# ZYNQ-DDR3L.net
KiCad netlist of a schematic drawn in Altium Designer
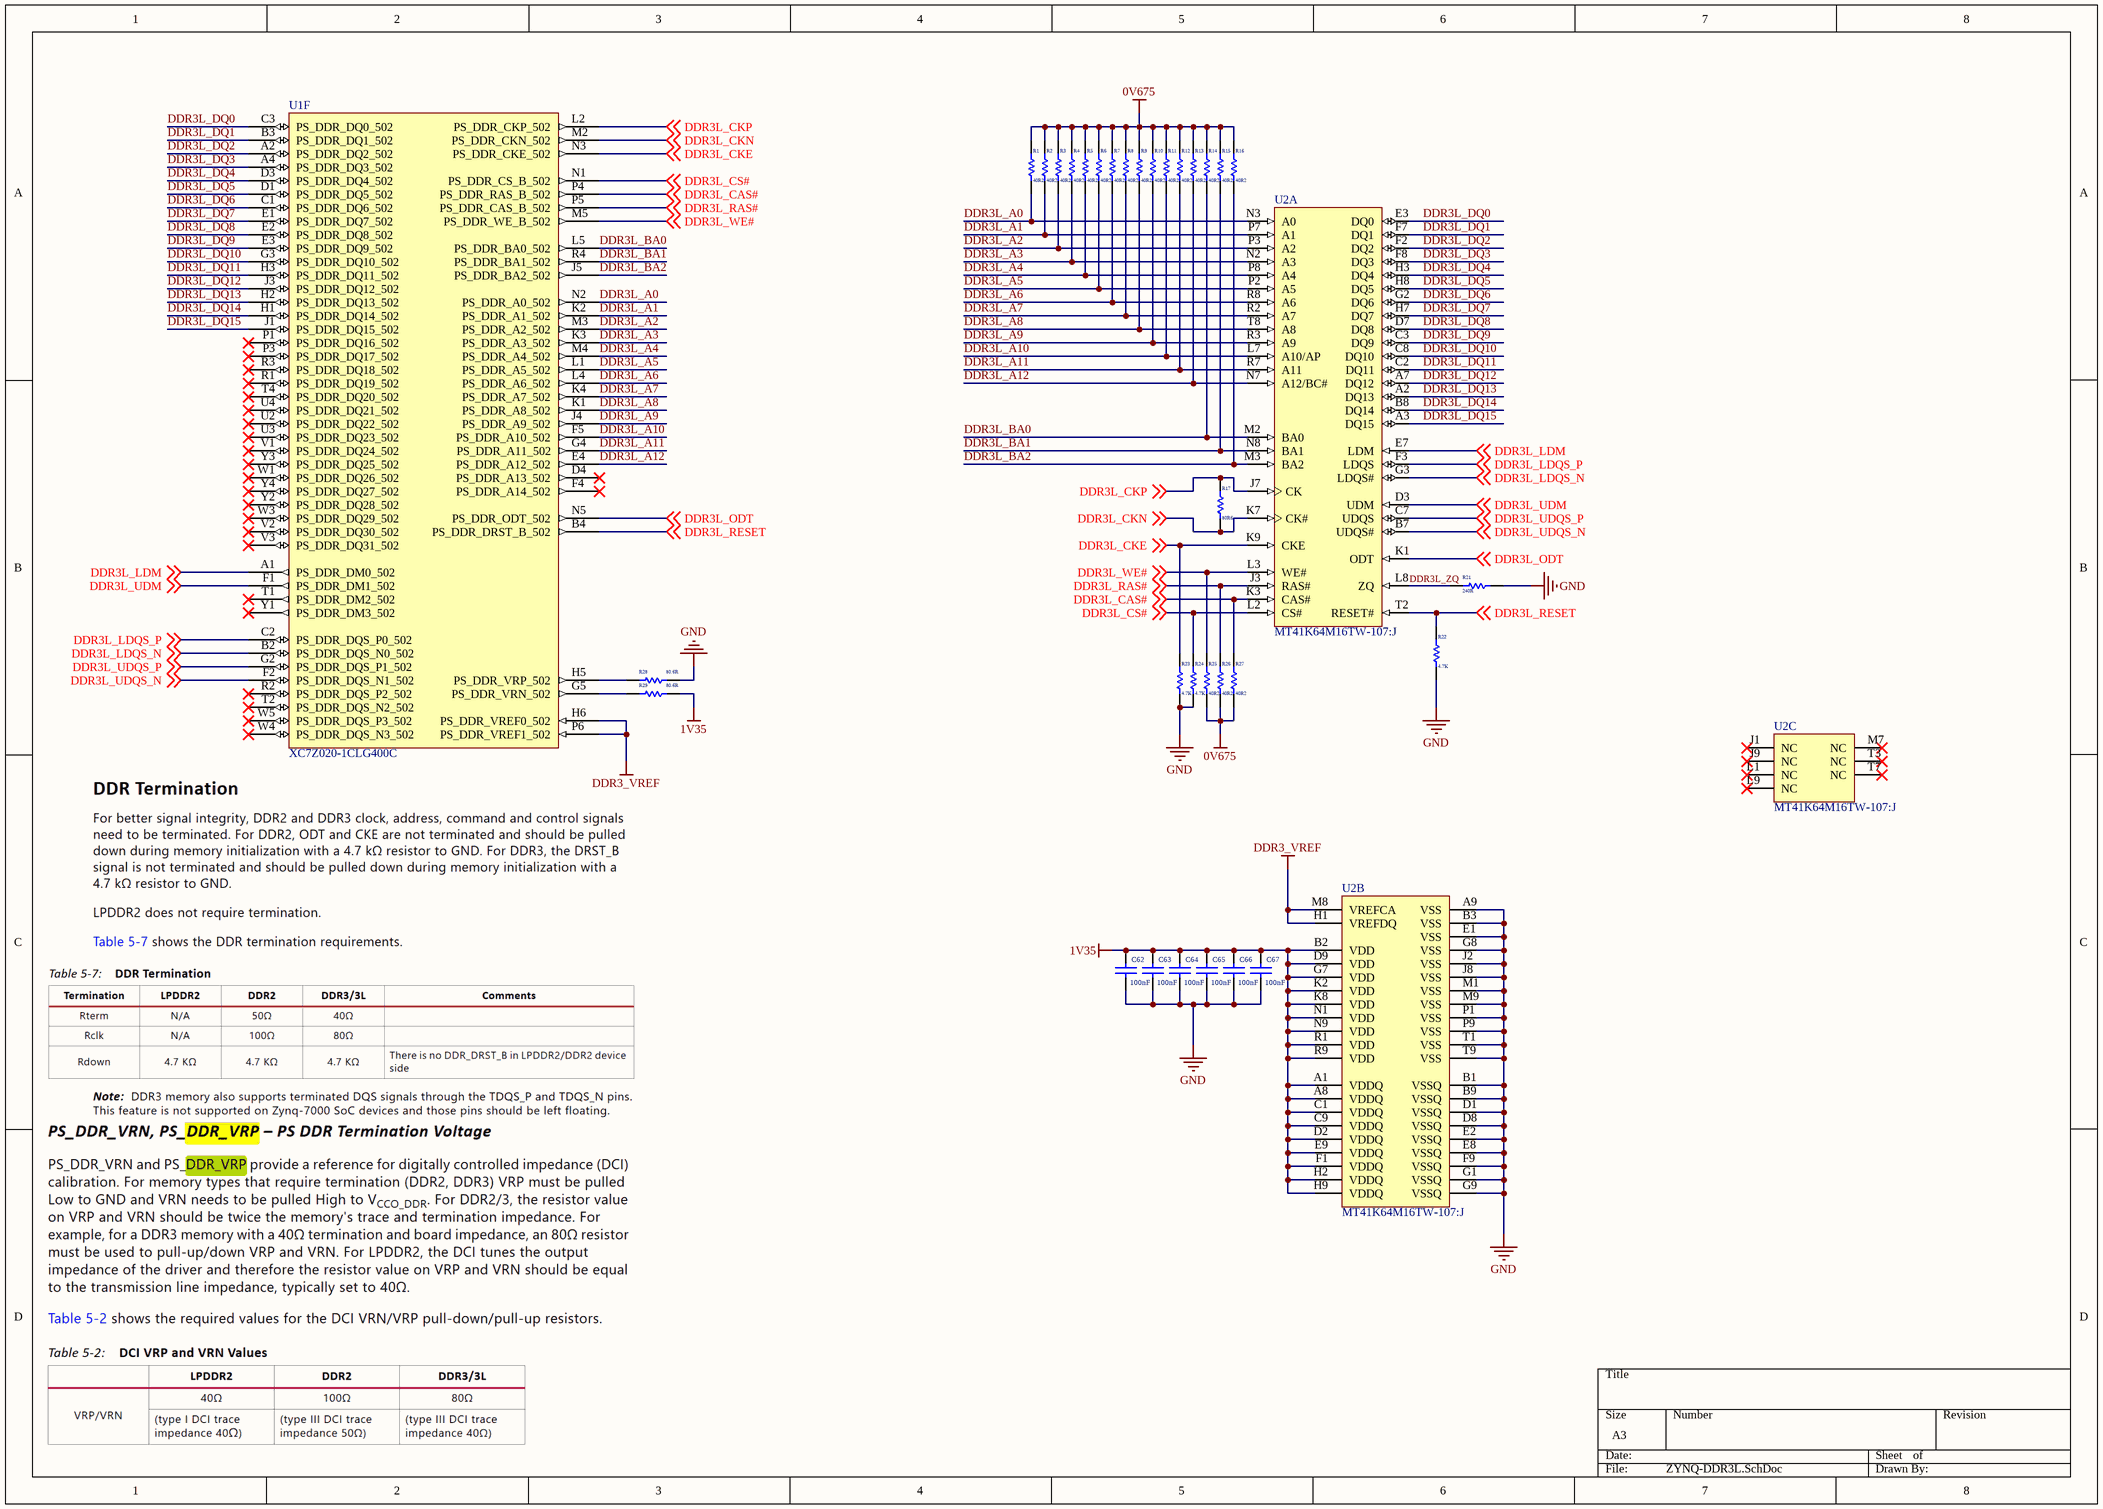
[diagram p0: ZYNQ-DDR3L.SchDoc]

(export (version "E")
  (design (tool "Eeschema 10.0.6"))
  (components
    (comp (ref "C62")
      (value "100nF")
      (footprint "CAPC1005X55X25LL05T10")
      (fields (field (name "PART NUMBER") "GRM155R71H104KE14D") (field (name "MANUFACTURER") "Murata"))
      (libsource (lib "Altium Content Vault") (part "CAP"))
    )
    (comp (ref "C63")
      (value "100nF")
      (footprint "CAPC1005X55X25LL05T10")
      (fields (field (name "PART NUMBER") "GRM155R71H104KE14D") (field (name "MANUFACTURER") "Murata"))
      (libsource (lib "Altium Content Vault") (part "CAP"))
    )
    (comp (ref "C64")
      (value "100nF")
      (footprint "CAPC1005X55X25LL05T10")
      (fields (field (name "PART NUMBER") "GRM155R71H104KE14D") (field (name "MANUFACTURER") "Murata"))
      (libsource (lib "Altium Content Vault") (part "CAP"))
    )
    (comp (ref "C65")
      (value "100nF")
      (footprint "CAPC1005X55X25LL05T10")
      (fields (field (name "PART NUMBER") "GRM155R71H104KE14D") (field (name "MANUFACTURER") "Murata"))
      (libsource (lib "Altium Content Vault") (part "CAP"))
    )
    (comp (ref "C66")
      (value "100nF")
      (footprint "CAPC1005X55X25LL05T10")
      (fields (field (name "PART NUMBER") "GRM155R71H104KE14D") (field (name "MANUFACTURER") "Murata"))
      (libsource (lib "Altium Content Vault") (part "CAP"))
    )
    (comp (ref "C67")
      (value "100nF")
      (footprint "CAPC1005X55X25LL05T10")
      (fields (field (name "PART NUMBER") "GRM155R71H104KE14D") (field (name "MANUFACTURER") "Murata"))
      (libsource (lib "Altium Content Vault") (part "CAP"))
    )
    (comp (ref "R1")
      (value "40R2")
      (footprint "RESC1005X40X25LL05T05")
      (fields (field (name "MANUFACTURER") "Panasonic") (field (name "PART NUMBER") "ERJ-2RKF40R2X"))
      (libsource (lib "Altium Content Vault") (part "RES"))
    )
    (comp (ref "R2")
      (value "40R2")
      (footprint "RESC1005X40X25LL05T05")
      (fields (field (name "MANUFACTURER") "Panasonic") (field (name "PART NUMBER") "ERJ-2RKF40R2X"))
      (libsource (lib "Altium Content Vault") (part "RES"))
    )
    (comp (ref "R3")
      (value "40R2")
      (footprint "RESC1005X40X25LL05T05")
      (fields (field (name "MANUFACTURER") "Panasonic") (field (name "PART NUMBER") "ERJ-2RKF40R2X"))
      (libsource (lib "Altium Content Vault") (part "RES"))
    )
    (comp (ref "R4")
      (value "40R2")
      (footprint "RESC1005X40X25LL05T05")
      (fields (field (name "MANUFACTURER") "Panasonic") (field (name "PART NUMBER") "ERJ-2RKF40R2X"))
      (libsource (lib "Altium Content Vault") (part "RES"))
    )
    (comp (ref "R5")
      (value "40R2")
      (footprint "RESC1005X40X25LL05T05")
      (fields (field (name "MANUFACTURER") "Panasonic") (field (name "PART NUMBER") "ERJ-2RKF40R2X"))
      (libsource (lib "Altium Content Vault") (part "RES"))
    )
    (comp (ref "R6")
      (value "40R2")
      (footprint "RESC1005X40X25LL05T05")
      (fields (field (name "MANUFACTURER") "Panasonic") (field (name "PART NUMBER") "ERJ-2RKF40R2X"))
      (libsource (lib "Altium Content Vault") (part "RES"))
    )
    (comp (ref "R7")
      (value "40R2")
      (footprint "RESC1005X40X25LL05T05")
      (fields (field (name "MANUFACTURER") "Panasonic") (field (name "PART NUMBER") "ERJ-2RKF40R2X"))
      (libsource (lib "Altium Content Vault") (part "RES"))
    )
    (comp (ref "R8")
      (value "40R2")
      (footprint "RESC1005X40X25LL05T05")
      (fields (field (name "MANUFACTURER") "Panasonic") (field (name "PART NUMBER") "ERJ-2RKF40R2X"))
      (libsource (lib "Altium Content Vault") (part "RES"))
    )
    (comp (ref "R9")
      (value "40R2")
      (footprint "RESC1005X40X25LL05T05")
      (fields (field (name "MANUFACTURER") "Panasonic") (field (name "PART NUMBER") "ERJ-2RKF40R2X"))
      (libsource (lib "Altium Content Vault") (part "RES"))
    )
    (comp (ref "R10")
      (value "40R2")
      (footprint "RESC1005X40X25LL05T05")
      (fields (field (name "MANUFACTURER") "Panasonic") (field (name "PART NUMBER") "ERJ-2RKF40R2X"))
      (libsource (lib "Altium Content Vault") (part "RES"))
    )
    (comp (ref "R11")
      (value "40R2")
      (footprint "RESC1005X40X25LL05T05")
      (fields (field (name "MANUFACTURER") "Panasonic") (field (name "PART NUMBER") "ERJ-2RKF40R2X"))
      (libsource (lib "Altium Content Vault") (part "RES"))
    )
    (comp (ref "R12")
      (value "40R2")
      (footprint "RESC1005X40X25LL05T05")
      (fields (field (name "MANUFACTURER") "Panasonic") (field (name "PART NUMBER") "ERJ-2RKF40R2X"))
      (libsource (lib "Altium Content Vault") (part "RES"))
    )
    (comp (ref "R13")
      (value "40R2")
      (footprint "RESC1005X40X25LL05T05")
      (fields (field (name "MANUFACTURER") "Panasonic") (field (name "PART NUMBER") "ERJ-2RKF40R2X"))
      (libsource (lib "Altium Content Vault") (part "RES"))
    )
    (comp (ref "R14")
      (value "40R2")
      (footprint "RESC1005X40X25LL05T05")
      (fields (field (name "MANUFACTURER") "Panasonic") (field (name "PART NUMBER") "ERJ-2RKF40R2X"))
      (libsource (lib "Altium Content Vault") (part "RES"))
    )
    (comp (ref "R15")
      (value "40R2")
      (footprint "RESC1005X40X25LL05T05")
      (fields (field (name "MANUFACTURER") "Panasonic") (field (name "PART NUMBER") "ERJ-2RKF40R2X"))
      (libsource (lib "Altium Content Vault") (part "RES"))
    )
    (comp (ref "R16")
      (value "40R2")
      (footprint "RESC1005X40X25LL05T05")
      (fields (field (name "MANUFACTURER") "Panasonic") (field (name "PART NUMBER") "ERJ-2RKF40R2X"))
      (libsource (lib "Altium Content Vault") (part "RES"))
    )
    (comp (ref "R17")
      (value "80R6")
      (footprint "RESC1005X40X25LL05T05")
      (fields (field (name "MANUFACTURER") "Panasonic") (field (name "PART NUMBER") "ERJ-2RKF40R2X"))
      (libsource (lib "Altium Content Vault") (part "RES"))
    )
    (comp (ref "R21")
      (value "240R")
      (footprint "RESC1005X40X25LL05T05")
      (fields (field (name "MANUFACTURER") "Panasonic") (field (name "PART NUMBER") "ERJ-2RKF40R2X"))
      (libsource (lib "Altium Content Vault") (part "RES"))
    )
    (comp (ref "R22")
      (value "4.7K")
      (footprint "RESC1005X40X25LL05T05")
      (fields (field (name "MANUFACTURER") "Panasonic") (field (name "PART NUMBER") "ERJ-2RKF40R2X"))
      (libsource (lib "Altium Content Vault") (part "RES"))
    )
    (comp (ref "R23")
      (value "4.7K")
      (footprint "RESC1005X40X25LL05T05")
      (fields (field (name "MANUFACTURER") "Panasonic") (field (name "PART NUMBER") "ERJ-2RKF40R2X"))
      (libsource (lib "Altium Content Vault") (part "RES"))
    )
    (comp (ref "R24")
      (value "4.7K")
      (footprint "RESC1005X40X25LL05T05")
      (fields (field (name "MANUFACTURER") "Panasonic") (field (name "PART NUMBER") "ERJ-2RKF40R2X"))
      (libsource (lib "Altium Content Vault") (part "RES"))
    )
    (comp (ref "R25")
      (value "40R2")
      (footprint "RESC1005X40X25LL05T05")
      (fields (field (name "MANUFACTURER") "Panasonic") (field (name "PART NUMBER") "ERJ-2RKF40R2X"))
      (libsource (lib "Altium Content Vault") (part "RES"))
    )
    (comp (ref "R26")
      (value "40R2")
      (footprint "RESC1005X40X25LL05T05")
      (fields (field (name "MANUFACTURER") "Panasonic") (field (name "PART NUMBER") "ERJ-2RKF40R2X"))
      (libsource (lib "Altium Content Vault") (part "RES"))
    )
    (comp (ref "R27")
      (value "40R2")
      (footprint "RESC1005X40X25LL05T05")
      (fields (field (name "MANUFACTURER") "Panasonic") (field (name "PART NUMBER") "ERJ-2RKF40R2X"))
      (libsource (lib "Altium Content Vault") (part "RES"))
    )
    (comp (ref "R28")
      (value "80.6R")
      (footprint "RESC1005X40X25LL05T05")
      (fields (field (name "MANUFACTURER") "Panasonic") (field (name "PART NUMBER") "ERJ-2RKF40R2X"))
      (libsource (lib "Altium Content Vault") (part "RES"))
    )
    (comp (ref "R29")
      (value "80.6R")
      (footprint "RESC1005X40X25LL05T05")
      (fields (field (name "MANUFACTURER") "Panasonic") (field (name "PART NUMBER") "ERJ-2RKF40R2X"))
      (libsource (lib "Altium Content Vault") (part "RES"))
    )
    (comp (ref "U1")
      (value "XC7Z020-1CLG400C")
      (footprint "CLG400")
      (fields (field (name "GENERIC PART NUMBER") "XC7Z020"))
      (libsource (lib "Altium Content Vault") (part "XNLX-XC7Z020-CLG400"))
    )
    (comp (ref "U2")
      (value "MT41K64M16TW-107:J")
      (footprint "MICT-TW-96")
      (description "DDR3L SDRAM, 8 Meg x 16 x 8 Bank, 1.07 ns, 0 to 95 degC, 96-Ball FBGA (TW), Pb-Free")
      (fields (field (name "MANUFACTURER") "Micron"))
      (libsource (lib "Altium Content Vault") (part "MICT-MT41K_1G-FBGA96"))
    )
  )
  (nets
    (net (code "1") (name "/DDR3L_A0") (class "Default")
      (node (ref "R1") (pin "1") (pinfunction "1_1") (pintype "passive"))
      (node (ref "U1") (pin "N2") (pinfunction "PS_DDR_A0_502_N2") (pintype "output"))
      (node (ref "U2") (pin "N3") (pinfunction "A0_N3") (pintype "input"))
    )
    (net (code "2") (name "/DDR3L_A1") (class "Default")
      (node (ref "R2") (pin "1") (pinfunction "1_1") (pintype "passive"))
      (node (ref "U1") (pin "K2") (pinfunction "PS_DDR_A1_502_K2") (pintype "output"))
      (node (ref "U2") (pin "P7") (pinfunction "A1_P7") (pintype "input"))
    )
    (net (code "3") (name "/DDR3L_A2") (class "Default")
      (node (ref "R3") (pin "1") (pinfunction "1_1") (pintype "passive"))
      (node (ref "U1") (pin "M3") (pinfunction "PS_DDR_A2_502_M3") (pintype "output"))
      (node (ref "U2") (pin "P3") (pinfunction "A2_P3") (pintype "input"))
    )
    (net (code "4") (name "/DDR3L_A3") (class "Default")
      (node (ref "R4") (pin "1") (pinfunction "1_1") (pintype "passive"))
      (node (ref "U1") (pin "K3") (pinfunction "PS_DDR_A3_502_K3") (pintype "output"))
      (node (ref "U2") (pin "N2") (pinfunction "A3_N2") (pintype "input"))
    )
    (net (code "5") (name "/DDR3L_A4") (class "Default")
      (node (ref "R5") (pin "1") (pinfunction "1_1") (pintype "passive"))
      (node (ref "U1") (pin "M4") (pinfunction "PS_DDR_A4_502_M4") (pintype "output"))
      (node (ref "U2") (pin "P8") (pinfunction "A4_P8") (pintype "input"))
    )
    (net (code "6") (name "/DDR3L_A5") (class "Default")
      (node (ref "R6") (pin "1") (pinfunction "1_1") (pintype "passive"))
      (node (ref "U1") (pin "L1") (pinfunction "PS_DDR_A5_502_L1") (pintype "output"))
      (node (ref "U2") (pin "P2") (pinfunction "A5_P2") (pintype "input"))
    )
    (net (code "7") (name "/DDR3L_A6") (class "Default")
      (node (ref "R7") (pin "1") (pinfunction "1_1") (pintype "passive"))
      (node (ref "U1") (pin "L4") (pinfunction "PS_DDR_A6_502_L4") (pintype "output"))
      (node (ref "U2") (pin "R8") (pinfunction "A6_R8") (pintype "input"))
    )
    (net (code "8") (name "/DDR3L_A7") (class "Default")
      (node (ref "R8") (pin "1") (pinfunction "1_1") (pintype "passive"))
      (node (ref "U1") (pin "K4") (pinfunction "PS_DDR_A7_502_K4") (pintype "output"))
      (node (ref "U2") (pin "R2") (pinfunction "A7_R2") (pintype "input"))
    )
    (net (code "9") (name "/DDR3L_A8") (class "Default")
      (node (ref "R9") (pin "1") (pinfunction "1_1") (pintype "passive"))
      (node (ref "U1") (pin "K1") (pinfunction "PS_DDR_A8_502_K1") (pintype "output"))
      (node (ref "U2") (pin "T8") (pinfunction "A8_T8") (pintype "input"))
    )
    (net (code "10") (name "/DDR3L_A9") (class "Default")
      (node (ref "R10") (pin "1") (pinfunction "1_1") (pintype "passive"))
      (node (ref "U1") (pin "J4") (pinfunction "PS_DDR_A9_502_J4") (pintype "output"))
      (node (ref "U2") (pin "R3") (pinfunction "A9_R3") (pintype "input"))
    )
    (net (code "11") (name "/DDR3L_A10") (class "Default")
      (node (ref "R11") (pin "1") (pinfunction "1_1") (pintype "passive"))
      (node (ref "U1") (pin "F5") (pinfunction "PS_DDR_A10_502_F5") (pintype "output"))
      (node (ref "U2") (pin "L7") (pinfunction "A10/AP_L7") (pintype "input"))
    )
    (net (code "12") (name "/DDR3L_A11") (class "Default")
      (node (ref "R12") (pin "1") (pinfunction "1_1") (pintype "passive"))
      (node (ref "U1") (pin "G4") (pinfunction "PS_DDR_A11_502_G4") (pintype "output"))
      (node (ref "U2") (pin "R7") (pinfunction "A11_R7") (pintype "input"))
    )
    (net (code "13") (name "/DDR3L_A12") (class "Default")
      (node (ref "R13") (pin "1") (pinfunction "1_1") (pintype "passive"))
      (node (ref "U1") (pin "E4") (pinfunction "PS_DDR_A12_502_E4") (pintype "output"))
      (node (ref "U2") (pin "N7") (pinfunction "A12/BC#_N7") (pintype "input"))
    )
    (net (code "14") (name "/DDR3L_BA0") (class "Default")
      (node (ref "R14") (pin "1") (pinfunction "1_1") (pintype "passive"))
      (node (ref "U1") (pin "L5") (pinfunction "PS_DDR_BA0_502_L5") (pintype "output"))
      (node (ref "U2") (pin "M2") (pinfunction "BA0_M2") (pintype "input"))
    )
    (net (code "15") (name "/DDR3L_BA1") (class "Default")
      (node (ref "R15") (pin "1") (pinfunction "1_1") (pintype "passive"))
      (node (ref "U1") (pin "R4") (pinfunction "PS_DDR_BA1_502_R4") (pintype "output"))
      (node (ref "U2") (pin "N8") (pinfunction "BA1_N8") (pintype "input"))
    )
    (net (code "16") (name "/DDR3L_BA2") (class "Default")
      (node (ref "R16") (pin "1") (pinfunction "1_1") (pintype "passive"))
      (node (ref "U1") (pin "J5") (pinfunction "PS_DDR_BA2_502_J5") (pintype "output"))
      (node (ref "U2") (pin "M3") (pinfunction "BA2_M3") (pintype "input"))
    )
    (net (code "17") (name "/DDR3L_DQ0") (class "Default")
      (node (ref "U1") (pin "C3") (pinfunction "PS_DDR_DQ0_502_C3") (pintype "bidirectional"))
      (node (ref "U2") (pin "E3") (pinfunction "DQ0_E3") (pintype "bidirectional"))
    )
    (net (code "18") (name "/DDR3L_DQ1") (class "Default")
      (node (ref "U1") (pin "B3") (pinfunction "PS_DDR_DQ1_502_B3") (pintype "bidirectional"))
      (node (ref "U2") (pin "F7") (pinfunction "DQ1_F7") (pintype "bidirectional"))
    )
    (net (code "19") (name "/DDR3L_DQ2") (class "Default")
      (node (ref "U1") (pin "A2") (pinfunction "PS_DDR_DQ2_502_A2") (pintype "bidirectional"))
      (node (ref "U2") (pin "F2") (pinfunction "DQ2_F2") (pintype "bidirectional"))
    )
    (net (code "20") (name "/DDR3L_DQ3") (class "Default")
      (node (ref "U1") (pin "A4") (pinfunction "PS_DDR_DQ3_502_A4") (pintype "bidirectional"))
      (node (ref "U2") (pin "F8") (pinfunction "DQ3_F8") (pintype "bidirectional"))
    )
    (net (code "21") (name "/DDR3L_DQ4") (class "Default")
      (node (ref "U1") (pin "D3") (pinfunction "PS_DDR_DQ4_502_D3") (pintype "bidirectional"))
      (node (ref "U2") (pin "H3") (pinfunction "DQ4_H3") (pintype "bidirectional"))
    )
    (net (code "22") (name "/DDR3L_DQ5") (class "Default")
      (node (ref "U1") (pin "D1") (pinfunction "PS_DDR_DQ5_502_D1") (pintype "bidirectional"))
      (node (ref "U2") (pin "H8") (pinfunction "DQ5_H8") (pintype "bidirectional"))
    )
    (net (code "23") (name "/DDR3L_DQ6") (class "Default")
      (node (ref "U1") (pin "C1") (pinfunction "PS_DDR_DQ6_502_C1") (pintype "bidirectional"))
      (node (ref "U2") (pin "G2") (pinfunction "DQ6_G2") (pintype "bidirectional"))
    )
    (net (code "24") (name "/DDR3L_DQ7") (class "Default")
      (node (ref "U1") (pin "E1") (pinfunction "PS_DDR_DQ7_502_E1") (pintype "bidirectional"))
      (node (ref "U2") (pin "H7") (pinfunction "DQ7_H7") (pintype "bidirectional"))
    )
    (net (code "25") (name "/DDR3L_DQ8") (class "Default")
      (node (ref "U1") (pin "E2") (pinfunction "PS_DDR_DQ8_502_E2") (pintype "bidirectional"))
      (node (ref "U2") (pin "D7") (pinfunction "DQ8_D7") (pintype "bidirectional"))
    )
    (net (code "26") (name "/DDR3L_DQ9") (class "Default")
      (node (ref "U1") (pin "E3") (pinfunction "PS_DDR_DQ9_502_E3") (pintype "bidirectional"))
      (node (ref "U2") (pin "C3") (pinfunction "DQ9_C3") (pintype "bidirectional"))
    )
    (net (code "27") (name "/DDR3L_DQ10") (class "Default")
      (node (ref "U1") (pin "G3") (pinfunction "PS_DDR_DQ10_502_G3") (pintype "bidirectional"))
      (node (ref "U2") (pin "C8") (pinfunction "DQ10_C8") (pintype "bidirectional"))
    )
    (net (code "28") (name "/DDR3L_DQ11") (class "Default")
      (node (ref "U1") (pin "H3") (pinfunction "PS_DDR_DQ11_502_H3") (pintype "bidirectional"))
      (node (ref "U2") (pin "C2") (pinfunction "DQ11_C2") (pintype "bidirectional"))
    )
    (net (code "29") (name "/DDR3L_DQ12") (class "Default")
      (node (ref "U1") (pin "J3") (pinfunction "PS_DDR_DQ12_502_J3") (pintype "bidirectional"))
      (node (ref "U2") (pin "A7") (pinfunction "DQ12_A7") (pintype "bidirectional"))
    )
    (net (code "30") (name "/DDR3L_DQ13") (class "Default")
      (node (ref "U1") (pin "H2") (pinfunction "PS_DDR_DQ13_502_H2") (pintype "bidirectional"))
      (node (ref "U2") (pin "A2") (pinfunction "DQ13_A2") (pintype "bidirectional"))
    )
    (net (code "31") (name "/DDR3L_DQ14") (class "Default")
      (node (ref "U1") (pin "H1") (pinfunction "PS_DDR_DQ14_502_H1") (pintype "bidirectional"))
      (node (ref "U2") (pin "B8") (pinfunction "DQ14_B8") (pintype "bidirectional"))
    )
    (net (code "32") (name "/DDR3L_DQ15") (class "Default")
      (node (ref "U1") (pin "J1") (pinfunction "PS_DDR_DQ15_502_J1") (pintype "bidirectional"))
      (node (ref "U2") (pin "A3") (pinfunction "DQ15_A3") (pintype "bidirectional"))
    )
    (net (code "33") (name "/DDR3L_ZQ") (class "Default")
      (node (ref "R21") (pin "2") (pinfunction "2_2") (pintype "passive"))
      (node (ref "U2") (pin "L8") (pinfunction "ZQ_L8") (pintype "input"))
    )
    (net (code "34") (name "0V675") (class "Default")
      (node (ref "R1") (pin "2") (pinfunction "2_2") (pintype "passive"))
      (node (ref "R10") (pin "2") (pinfunction "2_2") (pintype "passive"))
      (node (ref "R11") (pin "2") (pinfunction "2_2") (pintype "passive"))
      (node (ref "R12") (pin "2") (pinfunction "2_2") (pintype "passive"))
      (node (ref "R13") (pin "2") (pinfunction "2_2") (pintype "passive"))
      (node (ref "R14") (pin "2") (pinfunction "2_2") (pintype "passive"))
      (node (ref "R15") (pin "2") (pinfunction "2_2") (pintype "passive"))
      (node (ref "R16") (pin "2") (pinfunction "2_2") (pintype "passive"))
      (node (ref "R2") (pin "2") (pinfunction "2_2") (pintype "passive"))
      (node (ref "R25") (pin "1") (pinfunction "1_1") (pintype "passive"))
      (node (ref "R26") (pin "1") (pinfunction "1_1") (pintype "passive"))
      (node (ref "R27") (pin "1") (pinfunction "1_1") (pintype "passive"))
      (node (ref "R3") (pin "2") (pinfunction "2_2") (pintype "passive"))
      (node (ref "R4") (pin "2") (pinfunction "2_2") (pintype "passive"))
      (node (ref "R5") (pin "2") (pinfunction "2_2") (pintype "passive"))
      (node (ref "R6") (pin "2") (pinfunction "2_2") (pintype "passive"))
      (node (ref "R7") (pin "2") (pinfunction "2_2") (pintype "passive"))
      (node (ref "R8") (pin "2") (pinfunction "2_2") (pintype "passive"))
      (node (ref "R9") (pin "2") (pinfunction "2_2") (pintype "passive"))
    )
    (net (code "35") (name "1V35") (class "Default")
      (node (ref "C62") (pin "2") (pinfunction "2_2") (pintype "passive"))
      (node (ref "C63") (pin "2") (pinfunction "2_2") (pintype "passive"))
      (node (ref "C64") (pin "2") (pinfunction "2_2") (pintype "passive"))
      (node (ref "C65") (pin "2") (pinfunction "2_2") (pintype "passive"))
      (node (ref "C66") (pin "2") (pinfunction "2_2") (pintype "passive"))
      (node (ref "C67") (pin "2") (pinfunction "2_2") (pintype "passive"))
      (node (ref "R29") (pin "1") (pinfunction "1_1") (pintype "passive"))
      (node (ref "U2") (pin "A1") (pinfunction "VDDQ_A1") (pintype "power_in"))
      (node (ref "U2") (pin "A8") (pinfunction "VDDQ_A8") (pintype "power_in"))
      (node (ref "U2") (pin "B2") (pinfunction "VDD_B2") (pintype "power_in"))
      (node (ref "U2") (pin "C1") (pinfunction "VDDQ_C1") (pintype "power_in"))
      (node (ref "U2") (pin "C9") (pinfunction "VDDQ_C9") (pintype "power_in"))
      (node (ref "U2") (pin "D2") (pinfunction "VDDQ_D2") (pintype "power_in"))
      (node (ref "U2") (pin "D9") (pinfunction "VDD_D9") (pintype "power_in"))
      (node (ref "U2") (pin "E9") (pinfunction "VDDQ_E9") (pintype "power_in"))
      (node (ref "U2") (pin "F1") (pinfunction "VDDQ_F1") (pintype "power_in"))
      (node (ref "U2") (pin "G7") (pinfunction "VDD_G7") (pintype "power_in"))
      (node (ref "U2") (pin "H2") (pinfunction "VDDQ_H2") (pintype "power_in"))
      (node (ref "U2") (pin "H9") (pinfunction "VDDQ_H9") (pintype "power_in"))
      (node (ref "U2") (pin "K2") (pinfunction "VDD_K2") (pintype "power_in"))
      (node (ref "U2") (pin "K8") (pinfunction "VDD_K8") (pintype "power_in"))
      (node (ref "U2") (pin "N1") (pinfunction "VDD_N1") (pintype "power_in"))
      (node (ref "U2") (pin "N9") (pinfunction "VDD_N9") (pintype "power_in"))
      (node (ref "U2") (pin "R1") (pinfunction "VDD_R1") (pintype "power_in"))
      (node (ref "U2") (pin "R9") (pinfunction "VDD_R9") (pintype "power_in"))
    )
    (net (code "36") (name "DDR3L_CAS#") (class "Default")
      (node (ref "R27") (pin "2") (pinfunction "2_2") (pintype "passive"))
      (node (ref "U1") (pin "P4") (pinfunction "PS_DDR_RAS_B_502_P4") (pintype "output"))
      (node (ref "U2") (pin "K3") (pinfunction "CAS#_K3") (pintype "input"))
    )
    (net (code "37") (name "DDR3L_CKE") (class "Default")
      (node (ref "R23") (pin "2") (pinfunction "2_2") (pintype "passive"))
      (node (ref "U1") (pin "N3") (pinfunction "PS_DDR_CKE_502_N3") (pintype "output"))
      (node (ref "U2") (pin "K9") (pinfunction "CKE_K9") (pintype "input"))
    )
    (net (code "38") (name "DDR3L_CKN") (class "Default")
      (node (ref "R17") (pin "1") (pinfunction "1_1") (pintype "passive"))
      (node (ref "U1") (pin "M2") (pinfunction "PS_DDR_CKN_502_M2") (pintype "output"))
      (node (ref "U2") (pin "K7") (pinfunction "CK#_K7") (pintype "input"))
    )
    (net (code "39") (name "DDR3L_CKP") (class "Default")
      (node (ref "R17") (pin "2") (pinfunction "2_2") (pintype "passive"))
      (node (ref "U1") (pin "L2") (pinfunction "PS_DDR_CKP_502_L2") (pintype "output"))
      (node (ref "U2") (pin "J7") (pinfunction "CK_J7") (pintype "input"))
    )
    (net (code "40") (name "DDR3L_CS#") (class "Default")
      (node (ref "R24") (pin "2") (pinfunction "2_2") (pintype "passive"))
      (node (ref "U1") (pin "N1") (pinfunction "PS_DDR_CS_B_502_N1") (pintype "output"))
      (node (ref "U2") (pin "L2") (pinfunction "CS#_L2") (pintype "input"))
    )
    (net (code "41") (name "DDR3L_LDM") (class "Default")
      (node (ref "U1") (pin "A1") (pinfunction "PS_DDR_DM0_502_A1") (pintype "output"))
      (node (ref "U2") (pin "E7") (pinfunction "LDM_E7") (pintype "input"))
    )
    (net (code "42") (name "DDR3L_LDQS_N") (class "Default")
      (node (ref "U1") (pin "B2") (pinfunction "PS_DDR_DQS_N0_502_B2") (pintype "bidirectional"))
      (node (ref "U2") (pin "G3") (pinfunction "LDQS#_G3") (pintype "bidirectional"))
    )
    (net (code "43") (name "DDR3L_LDQS_P") (class "Default")
      (node (ref "U1") (pin "C2") (pinfunction "PS_DDR_DQS_P0_502_C2") (pintype "bidirectional"))
      (node (ref "U2") (pin "F3") (pinfunction "LDQS_F3") (pintype "bidirectional"))
    )
    (net (code "44") (name "DDR3L_ODT") (class "Default")
      (node (ref "U1") (pin "N5") (pinfunction "PS_DDR_ODT_502_N5") (pintype "output"))
      (node (ref "U2") (pin "K1") (pinfunction "ODT_K1") (pintype "input"))
    )
    (net (code "45") (name "DDR3L_RAS#") (class "Default")
      (node (ref "R26") (pin "2") (pinfunction "2_2") (pintype "passive"))
      (node (ref "U1") (pin "P5") (pinfunction "PS_DDR_CAS_B_502_P5") (pintype "output"))
      (node (ref "U2") (pin "J3") (pinfunction "RAS#_J3") (pintype "input"))
    )
    (net (code "46") (name "DDR3L_RESET") (class "Default")
      (node (ref "R22") (pin "2") (pinfunction "2_2") (pintype "passive"))
      (node (ref "U1") (pin "B4") (pinfunction "PS_DDR_DRST_B_502_B4") (pintype "output"))
      (node (ref "U2") (pin "T2") (pinfunction "RESET#_T2") (pintype "input"))
    )
    (net (code "47") (name "DDR3L_UDM") (class "Default")
      (node (ref "U1") (pin "F1") (pinfunction "PS_DDR_DM1_502_F1") (pintype "output"))
      (node (ref "U2") (pin "D3") (pinfunction "UDM_D3") (pintype "input"))
    )
    (net (code "48") (name "DDR3L_UDQS_N") (class "Default")
      (node (ref "U1") (pin "F2") (pinfunction "PS_DDR_DQS_N1_502_F2") (pintype "bidirectional"))
      (node (ref "U2") (pin "B7") (pinfunction "UDQS#_B7") (pintype "bidirectional"))
    )
    (net (code "49") (name "DDR3L_UDQS_P") (class "Default")
      (node (ref "U1") (pin "G2") (pinfunction "PS_DDR_DQS_P1_502_G2") (pintype "bidirectional"))
      (node (ref "U2") (pin "C7") (pinfunction "UDQS_C7") (pintype "bidirectional"))
    )
    (net (code "50") (name "DDR3L_WE#") (class "Default")
      (node (ref "R25") (pin "2") (pinfunction "2_2") (pintype "passive"))
      (node (ref "U1") (pin "M5") (pinfunction "PS_DDR_WE_B_502_M5") (pintype "output"))
      (node (ref "U2") (pin "L3") (pinfunction "WE#_L3") (pintype "input"))
    )
    (net (code "51") (name "DDR3_VREF") (class "Default")
      (node (ref "U1") (pin "H6") (pinfunction "PS_DDR_VREF0_502_H6") (pintype "input"))
      (node (ref "U1") (pin "P6") (pinfunction "PS_DDR_VREF1_502_P6") (pintype "input"))
      (node (ref "U2") (pin "H1") (pinfunction "VREFDQ_H1") (pintype "power_in"))
      (node (ref "U2") (pin "M8") (pinfunction "VREFCA_M8") (pintype "power_in"))
    )
    (net (code "52") (name "GND") (class "Default")
      (node (ref "C62") (pin "1") (pinfunction "1_1") (pintype "passive"))
      (node (ref "C63") (pin "1") (pinfunction "1_1") (pintype "passive"))
      (node (ref "C64") (pin "1") (pinfunction "1_1") (pintype "passive"))
      (node (ref "C65") (pin "1") (pinfunction "1_1") (pintype "passive"))
      (node (ref "C66") (pin "1") (pinfunction "1_1") (pintype "passive"))
      (node (ref "C67") (pin "1") (pinfunction "1_1") (pintype "passive"))
      (node (ref "R21") (pin "1") (pinfunction "1_1") (pintype "passive"))
      (node (ref "R22") (pin "1") (pinfunction "1_1") (pintype "passive"))
      (node (ref "R23") (pin "1") (pinfunction "1_1") (pintype "passive"))
      (node (ref "R24") (pin "1") (pinfunction "1_1") (pintype "passive"))
      (node (ref "R28") (pin "1") (pinfunction "1_1") (pintype "passive"))
      (node (ref "U2") (pin "A9") (pinfunction "VSS_A9") (pintype "power_in"))
      (node (ref "U2") (pin "B1") (pinfunction "VSSQ_B1") (pintype "power_in"))
      (node (ref "U2") (pin "B3") (pinfunction "VSS_B3") (pintype "power_in"))
      (node (ref "U2") (pin "B9") (pinfunction "VSSQ_B9") (pintype "power_in"))
      (node (ref "U2") (pin "D1") (pinfunction "VSSQ_D1") (pintype "power_in"))
      (node (ref "U2") (pin "D8") (pinfunction "VSSQ_D8") (pintype "power_in"))
      (node (ref "U2") (pin "E1") (pinfunction "VSS_E1") (pintype "power_in"))
      (node (ref "U2") (pin "E2") (pinfunction "VSSQ_E2") (pintype "power_in"))
      (node (ref "U2") (pin "E8") (pinfunction "VSSQ_E8") (pintype "power_in"))
      (node (ref "U2") (pin "F9") (pinfunction "VSSQ_F9") (pintype "power_in"))
      (node (ref "U2") (pin "G1") (pinfunction "VSSQ_G1") (pintype "power_in"))
      (node (ref "U2") (pin "G8") (pinfunction "VSS_G8") (pintype "power_in"))
      (node (ref "U2") (pin "G9") (pinfunction "VSSQ_G9") (pintype "power_in"))
      (node (ref "U2") (pin "J2") (pinfunction "VSS_J2") (pintype "power_in"))
      (node (ref "U2") (pin "J8") (pinfunction "VSS_J8") (pintype "power_in"))
      (node (ref "U2") (pin "M1") (pinfunction "VSS_M1") (pintype "power_in"))
      (node (ref "U2") (pin "M9") (pinfunction "VSS_M9") (pintype "power_in"))
      (node (ref "U2") (pin "P1") (pinfunction "VSS_P1") (pintype "power_in"))
      (node (ref "U2") (pin "P9") (pinfunction "VSS_P9") (pintype "power_in"))
      (node (ref "U2") (pin "T1") (pinfunction "VSS_T1") (pintype "power_in"))
      (node (ref "U2") (pin "T9") (pinfunction "VSS_T9") (pintype "power_in"))
    )
    (net (code "53") (name "Net-(U1F-PS_DDR_VRN_502)") (class "Default")
      (node (ref "R29") (pin "2") (pinfunction "2_2") (pintype "passive"))
      (node (ref "U1") (pin "G5") (pinfunction "PS_DDR_VRN_502_G5") (pintype "output"))
    )
    (net (code "54") (name "Net-(U1F-PS_DDR_VRP_502)") (class "Default")
      (node (ref "R28") (pin "2") (pinfunction "2_2") (pintype "passive"))
      (node (ref "U1") (pin "H5") (pinfunction "PS_DDR_VRP_502_H5") (pintype "output"))
    )
    (net (code "55") (name "unconnected-(U1F-PS_DDR_A13_502-PadD4)") (class "Default")
      (node (ref "U1") (pin "D4") (pinfunction "PS_DDR_A13_502_D4") (pintype "output+no_connect"))
    )
    (net (code "56") (name "unconnected-(U1F-PS_DDR_A14_502-PadF4)") (class "Default")
      (node (ref "U1") (pin "F4") (pinfunction "PS_DDR_A14_502_F4") (pintype "output+no_connect"))
    )
    (net (code "57") (name "unconnected-(U1F-PS_DDR_DM2_502-PadT1)") (class "Default")
      (node (ref "U1") (pin "T1") (pinfunction "PS_DDR_DM2_502_T1") (pintype "output+no_connect"))
    )
    (net (code "58") (name "unconnected-(U1F-PS_DDR_DM3_502-PadY1)") (class "Default")
      (node (ref "U1") (pin "Y1") (pinfunction "PS_DDR_DM3_502_Y1") (pintype "output+no_connect"))
    )
    (net (code "59") (name "unconnected-(U1F-PS_DDR_DQ16_502-PadP1)") (class "Default")
      (node (ref "U1") (pin "P1") (pinfunction "PS_DDR_DQ16_502_P1") (pintype "bidirectional+no_connect"))
    )
    (net (code "60") (name "unconnected-(U1F-PS_DDR_DQ17_502-PadP3)") (class "Default")
      (node (ref "U1") (pin "P3") (pinfunction "PS_DDR_DQ17_502_P3") (pintype "bidirectional+no_connect"))
    )
    (net (code "61") (name "unconnected-(U1F-PS_DDR_DQ18_502-PadR3)") (class "Default")
      (node (ref "U1") (pin "R3") (pinfunction "PS_DDR_DQ18_502_R3") (pintype "bidirectional+no_connect"))
    )
    (net (code "62") (name "unconnected-(U1F-PS_DDR_DQ19_502-PadR1)") (class "Default")
      (node (ref "U1") (pin "R1") (pinfunction "PS_DDR_DQ19_502_R1") (pintype "bidirectional+no_connect"))
    )
    (net (code "63") (name "unconnected-(U1F-PS_DDR_DQ20_502-PadT4)") (class "Default")
      (node (ref "U1") (pin "T4") (pinfunction "PS_DDR_DQ20_502_T4") (pintype "bidirectional+no_connect"))
    )
    (net (code "64") (name "unconnected-(U1F-PS_DDR_DQ21_502-PadU4)") (class "Default")
      (node (ref "U1") (pin "U4") (pinfunction "PS_DDR_DQ21_502_U4") (pintype "bidirectional+no_connect"))
    )
    (net (code "65") (name "unconnected-(U1F-PS_DDR_DQ22_502-PadU2)") (class "Default")
      (node (ref "U1") (pin "U2") (pinfunction "PS_DDR_DQ22_502_U2") (pintype "bidirectional+no_connect"))
    )
    (net (code "66") (name "unconnected-(U1F-PS_DDR_DQ23_502-PadU3)") (class "Default")
      (node (ref "U1") (pin "U3") (pinfunction "PS_DDR_DQ23_502_U3") (pintype "bidirectional+no_connect"))
    )
    (net (code "67") (name "unconnected-(U1F-PS_DDR_DQ24_502-PadV1)") (class "Default")
      (node (ref "U1") (pin "V1") (pinfunction "PS_DDR_DQ24_502_V1") (pintype "bidirectional+no_connect"))
    )
    (net (code "68") (name "unconnected-(U1F-PS_DDR_DQ25_502-PadY3)") (class "Default")
      (node (ref "U1") (pin "Y3") (pinfunction "PS_DDR_DQ25_502_Y3") (pintype "bidirectional+no_connect"))
    )
    (net (code "69") (name "unconnected-(U1F-PS_DDR_DQ26_502-PadW1)") (class "Default")
      (node (ref "U1") (pin "W1") (pinfunction "PS_DDR_DQ26_502_W1") (pintype "bidirectional+no_connect"))
    )
    (net (code "70") (name "unconnected-(U1F-PS_DDR_DQ27_502-PadY4)") (class "Default")
      (node (ref "U1") (pin "Y4") (pinfunction "PS_DDR_DQ27_502_Y4") (pintype "bidirectional+no_connect"))
    )
    (net (code "71") (name "unconnected-(U1F-PS_DDR_DQ28_502-PadY2)") (class "Default")
      (node (ref "U1") (pin "Y2") (pinfunction "PS_DDR_DQ28_502_Y2") (pintype "bidirectional+no_connect"))
    )
    (net (code "72") (name "unconnected-(U1F-PS_DDR_DQ29_502-PadW3)") (class "Default")
      (node (ref "U1") (pin "W3") (pinfunction "PS_DDR_DQ29_502_W3") (pintype "bidirectional+no_connect"))
    )
    (net (code "73") (name "unconnected-(U1F-PS_DDR_DQ30_502-PadV2)") (class "Default")
      (node (ref "U1") (pin "V2") (pinfunction "PS_DDR_DQ30_502_V2") (pintype "bidirectional+no_connect"))
    )
    (net (code "74") (name "unconnected-(U1F-PS_DDR_DQ31_502-PadV3)") (class "Default")
      (node (ref "U1") (pin "V3") (pinfunction "PS_DDR_DQ31_502_V3") (pintype "bidirectional+no_connect"))
    )
    (net (code "75") (name "unconnected-(U1F-PS_DDR_DQS_N2_502-PadT2)") (class "Default")
      (node (ref "U1") (pin "T2") (pinfunction "PS_DDR_DQS_N2_502_T2") (pintype "bidirectional+no_connect"))
    )
    (net (code "76") (name "unconnected-(U1F-PS_DDR_DQS_N3_502-PadW4)") (class "Default")
      (node (ref "U1") (pin "W4") (pinfunction "PS_DDR_DQS_N3_502_W4") (pintype "bidirectional+no_connect"))
    )
    (net (code "77") (name "unconnected-(U1F-PS_DDR_DQS_P2_502-PadR2)") (class "Default")
      (node (ref "U1") (pin "R2") (pinfunction "PS_DDR_DQS_P2_502_R2") (pintype "bidirectional+no_connect"))
    )
    (net (code "78") (name "unconnected-(U1F-PS_DDR_DQS_P3_502-PadW5)") (class "Default")
      (node (ref "U1") (pin "W5") (pinfunction "PS_DDR_DQS_P3_502_W5") (pintype "bidirectional+no_connect"))
    )
    (net (code "79") (name "unconnected-(U2C-NC-PadJ1)") (class "Default")
      (node (ref "U2") (pin "J1") (pinfunction "NC_J1") (pintype "passive+no_connect"))
    )
    (net (code "80") (name "unconnected-(U2C-NC-PadJ9)") (class "Default")
      (node (ref "U2") (pin "J9") (pinfunction "NC_J9") (pintype "passive+no_connect"))
    )
    (net (code "81") (name "unconnected-(U2C-NC-PadL1)") (class "Default")
      (node (ref "U2") (pin "L1") (pinfunction "NC_L1") (pintype "passive+no_connect"))
    )
    (net (code "82") (name "unconnected-(U2C-NC-PadL9)") (class "Default")
      (node (ref "U2") (pin "L9") (pinfunction "NC_L9") (pintype "passive+no_connect"))
    )
    (net (code "83") (name "unconnected-(U2C-NC-PadM7)") (class "Default")
      (node (ref "U2") (pin "M7") (pinfunction "NC_M7") (pintype "passive+no_connect"))
    )
    (net (code "84") (name "unconnected-(U2C-NC-PadT3)") (class "Default")
      (node (ref "U2") (pin "T3") (pinfunction "NC_T3") (pintype "passive+no_connect"))
    )
    (net (code "85") (name "unconnected-(U2C-NC-PadT7)") (class "Default")
      (node (ref "U2") (pin "T7") (pinfunction "NC_T7") (pintype "passive+no_connect"))
    )
  )
)
